# self-balancing-robot.net
KiCad netlist of a schematic drawn in EasyEDA Pro
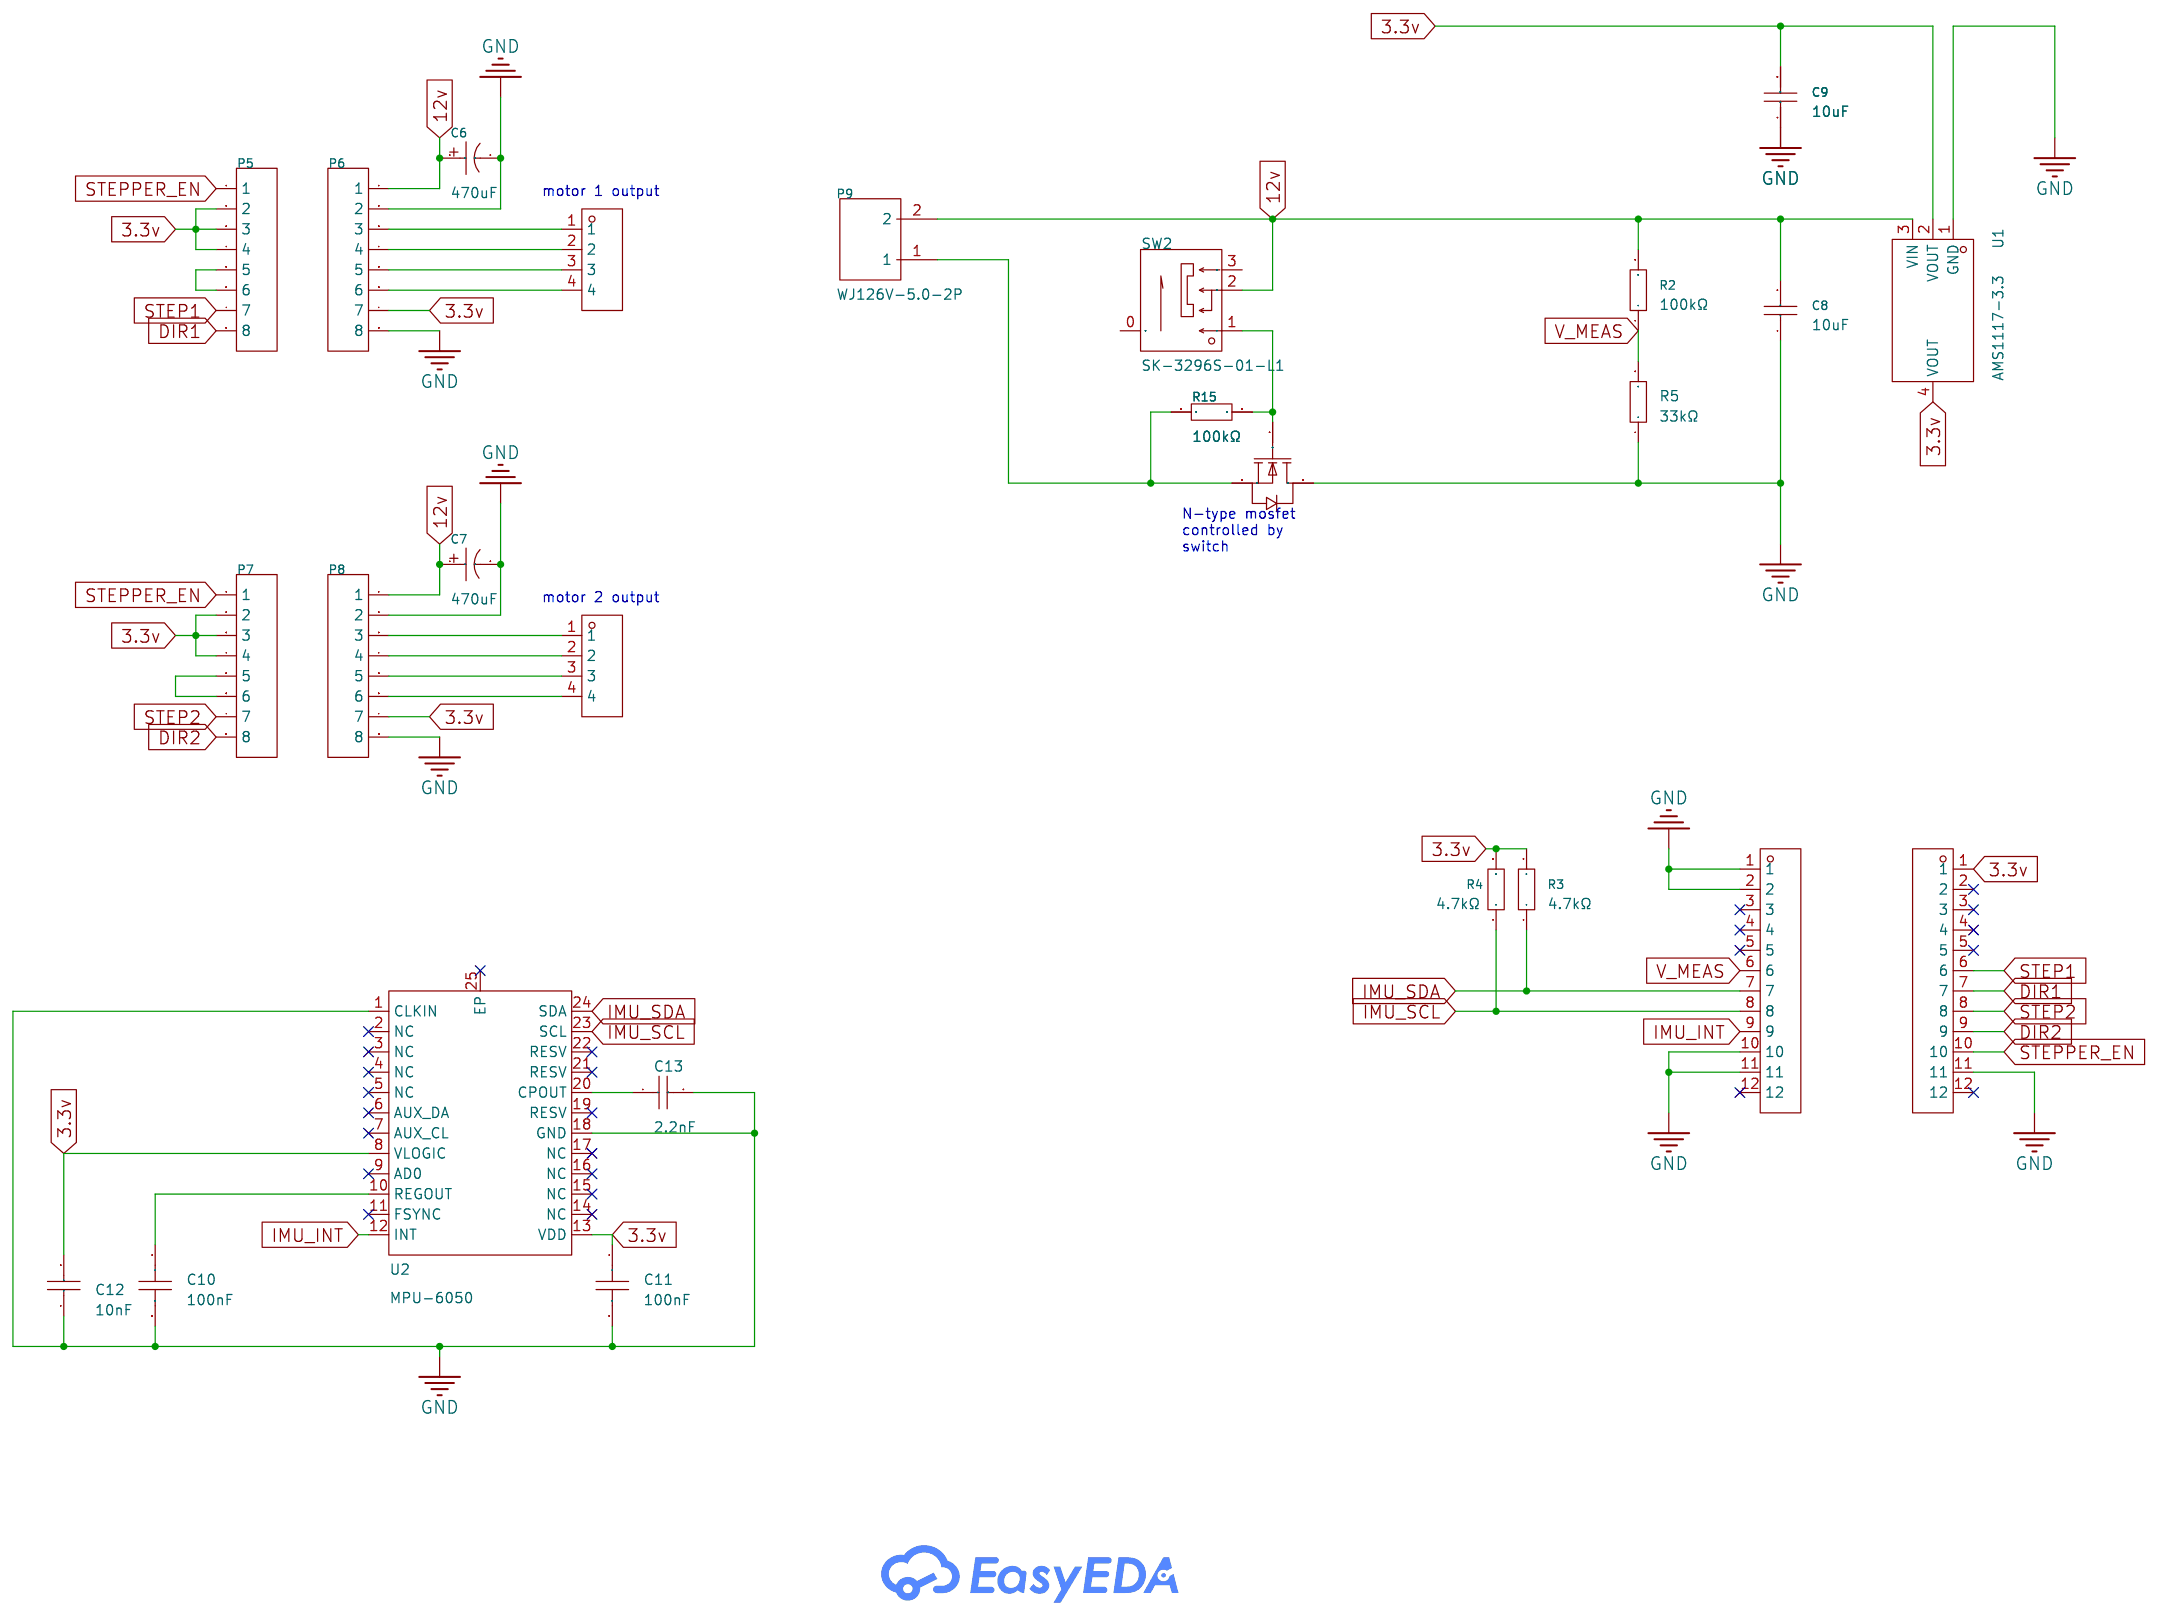
[diagram p0: schematic sheet]

(export (version "E")
  (design (tool "Eeschema 10.0.6"))
  (components
    (comp (ref "C6")
      (value "470uF")
      (footprint "easyedapro:CAP-TH_BD8.0-P3.50-D0.6-FD")
      (fields
        (field (name "Manufacturer Part") "KM477M016F12RR0VH2FP0")
        (field (name "Manufacturer") "CX(承兴)")
      )
      (libsource (lib "easyedapro") (part "470uf16v"))
    )
    (comp (ref "C7")
      (value "470uF")
      (footprint "easyedapro:CAP-TH_BD8.0-P3.50-D0.6-FD")
      (fields
        (field (name "Manufacturer Part") "KM477M016F12RR0VH2FP0")
        (field (name "Manufacturer") "CX(承兴)")
      )
      (libsource (lib "easyedapro") (part "470uf16v"))
    )
    (comp (ref "C8")
      (value "10uF")
      (footprint "easyedapro:C1206")
      (fields
        (field (name "Manufacturer Part") "CL31A106KBHNNNE")
        (field (name "Manufacturer") "SAMSUNG(三星)")
      )
      (libsource (lib "easyedapro") (part "CL31A106KBHNNNE"))
    )
    (comp (ref "C9")
      (value "10uF")
      (footprint "easyedapro:C1206")
      (fields
        (field (name "Manufacturer Part") "CL31A106KBHNNNE")
        (field (name "Manufacturer") "SAMSUNG(三星)")
      )
      (libsource (lib "easyedapro") (part "CL31A106KBHNNNE"))
    )
    (comp (ref "C10")
      (value "100nF")
      (footprint "easyedapro:C0402")
      (description "Capacitance:100nF Tolerance:±10% Tolerance:±10% Voltage Rating:16V Temperature Coefficient:X7R")
      (fields
        (field (name "Manufacturer Part") "CL05B104KO5NNNC")
        (field (name "Manufacturer") "SAMSUNG(三星)")
      )
      (libsource (lib "easyedapro") (part "CL05B104KO5NNNC"))
    )
    (comp (ref "C11")
      (value "100nF")
      (footprint "easyedapro:C0402")
      (description "Capacitance:100nF Tolerance:±10% Tolerance:±10% Voltage Rating:16V Temperature Coefficient:X7R")
      (fields
        (field (name "Manufacturer Part") "CL05B104KO5NNNC")
        (field (name "Manufacturer") "SAMSUNG(三星)")
      )
      (libsource (lib "easyedapro") (part "CL05B104KO5NNNC"))
    )
    (comp (ref "C12")
      (value "10nF")
      (footprint "easyedapro:C0402")
      (description "Capacitance:10nF Tolerance:±10% Tolerance:±10% Voltage Rating:50V Temperature Coefficient:X7R")
      (fields
        (field (name "Manufacturer Part") "CL05B103KB5NNNC")
        (field (name "Manufacturer") "SAMSUNG(三星)")
      )
      (libsource (lib "easyedapro") (part "CL05B103KB5NNNC"))
    )
    (comp (ref "C13")
      (value "2.2nF")
      (footprint "easyedapro:C0402")
      (description "Capacitance:2.2nF Tolerance:±10% Tolerance:±10% Voltage Rating:50V Temperature Coefficient:X7R")
      (fields (field (name "Manufacturer Part") "0402B222K500NT") (field (name "Manufacturer") "FH(风华)"))
      (libsource (lib "easyedapro") (part "0402B222K500NT"))
    )
    (comp (ref "H1")
      (value "PM2.54-1*12")
      (footprint "easyedapro:HDR-TH_12P-P2.54-V-F")
      (fields (field (name "Manufacturer") "ZHOURI(洲日)"))
      (libsource (lib "easyedapro") (part "PM2.54-1*12"))
    )
    (comp (ref "H2")
      (value "PM2.54-1*12")
      (footprint "easyedapro:HDR-TH_12P-P2.54-V-F")
      (fields (field (name "Manufacturer") "ZHOURI(洲日)"))
      (libsource (lib "easyedapro") (part "PM2.54-1*12"))
    )
    (comp (ref "H5")
      (value "2.54-1*4P母")
      (footprint "easyedapro:HDR-TH_4P-P2.54-V-F")
      (fields (field (name "Manufacturer") "BOOMELE(博穆精密)"))
      (libsource (lib "easyedapro") (part "2.54-1*4P母"))
    )
    (comp (ref "H6")
      (value "2.54-1*4P母")
      (footprint "easyedapro:HDR-TH_4P-P2.54-V-F")
      (fields (field (name "Manufacturer") "BOOMELE(博穆精密)"))
      (libsource (lib "easyedapro") (part "2.54-1*4P母"))
    )
    (comp (ref "P5")
      (value "2.54-1*8P母环保")
      (footprint "easyedapro:HDR-TH_8P-P2.54-V-F-1")
      (fields (field (name "Manufacturer") "BOOMELE(博穆精密)"))
      (libsource (lib "easyedapro") (part "Header-Female-2.54_1x8"))
    )
    (comp (ref "P6")
      (value "2.54-1*8P母环保")
      (footprint "easyedapro:HDR-TH_8P-P2.54-V-F-1")
      (fields (field (name "Manufacturer") "BOOMELE(博穆精密)"))
      (libsource (lib "easyedapro") (part "Header-Female-2.54_1x8"))
    )
    (comp (ref "P7")
      (value "2.54-1*8P母环保")
      (footprint "easyedapro:HDR-TH_8P-P2.54-V-F-1")
      (fields (field (name "Manufacturer") "BOOMELE(博穆精密)"))
      (libsource (lib "easyedapro") (part "Header-Female-2.54_1x8"))
    )
    (comp (ref "P8")
      (value "2.54-1*8P母环保")
      (footprint "easyedapro:HDR-TH_8P-P2.54-V-F-1")
      (fields (field (name "Manufacturer") "BOOMELE(博穆精密)"))
      (libsource (lib "easyedapro") (part "Header-Female-2.54_1x8"))
    )
    (comp (ref "P9")
      (value "WJ126V-5.0-2P")
      (footprint "easyedapro:CONN-TH_WJ126V-5.0-2P")
      (fields (field (name "Manufacturer") "KANGNEX(康奈克斯电气)"))
      (libsource (lib "easyedapro") (part "WJ126V-5.0-2P"))
    )
    (comp (ref "Q1")
      (value "AO3400A")
      (footprint "easyedapro:SOT-23-3_L2.9-W1.6-P1.90-LS2.8-BR")
      (fields (field (name "Manufacturer") "AOS"))
      (libsource (lib "easyedapro") (part "AO3400A"))
    )
    (comp (ref "R2")
      (value "100kΩ")
      (footprint "easyedapro:R0402")
      (fields
        (field (name "Manufacturer Part") "0402WGF1003TCE")
        (field (name "Manufacturer") "UNI-ROYAL(厚声)")
      )
      (libsource (lib "easyedapro") (part "0402WGF1003TCE"))
    )
    (comp (ref "R3")
      (value "4.7kΩ")
      (footprint "easyedapro:R0402")
      (fields
        (field (name "Manufacturer Part") "0402WGF4701TCE")
        (field (name "Manufacturer") "UNI-ROYAL(厚声)")
      )
      (libsource (lib "easyedapro") (part "0402WGF4701TCE"))
    )
    (comp (ref "R4")
      (value "4.7kΩ")
      (footprint "easyedapro:R0402")
      (fields
        (field (name "Manufacturer Part") "0402WGF4701TCE")
        (field (name "Manufacturer") "UNI-ROYAL(厚声)")
      )
      (libsource (lib "easyedapro") (part "0402WGF4701TCE"))
    )
    (comp (ref "R5")
      (value "33kΩ")
      (footprint "easyedapro:R0402")
      (fields
        (field (name "Manufacturer Part") "0402WGF3302TCE")
        (field (name "Manufacturer") "UNI-ROYAL(厚声)")
      )
      (libsource (lib "easyedapro") (part "0402WGF3302TCE"))
    )
    (comp (ref "R15")
      (value "100kΩ")
      (footprint "easyedapro:R0402")
      (fields
        (field (name "Manufacturer Part") "0402WGF1003TCE")
        (field (name "Manufacturer") "UNI-ROYAL(厚声)")
      )
      (libsource (lib "easyedapro") (part "0402WGF1003TCE"))
    )
    (comp (ref "SW2")
      (value "SK-3296S-01-L1")
      (footprint "easyedapro:SW-SMD_3P-P1.50_L2.7-W6.6")
      (fields (field (name "Manufacturer") "XKB Connectivity(中国星坤)"))
      (libsource (lib "easyedapro") (part "SK-3296S-01-L1"))
    )
    (comp (ref "U1")
      (value "AMS1117-3.3")
      (footprint "easyedapro:SOT-223-3_L6.5-W3.4-P2.30-LS7.0-BR")
      (fields (field (name "Manufacturer") "AMS"))
      (libsource (lib "easyedapro") (part "AMS1117-3.3"))
    )
    (comp (ref "U2")
      (value "MPU-6050")
      (footprint "easyedapro:QFN-24_L4.0-W4.0-P0.50-BL-EP2.7")
      (fields (field (name "Manufacturer") "TDK InvenSense(应美盛)"))
      (libsource (lib "easyedapro") (part "MPU-6050_C24112"))
    )
  )
  (nets
    (net (code "1") (name "3.3v") (class "Default")
      (node (ref "C11") (pin "1") (pinfunction "1_1") (pintype "unspecified"))
      (node (ref "C12") (pin "2") (pinfunction "2_2") (pintype "input"))
      (node (ref "C9") (pin "2") (pinfunction "2_2") (pintype "input"))
      (node (ref "H2") (pin "1") (pinfunction "1_1") (pintype "unspecified"))
      (node (ref "P5") (pin "2") (pinfunction "2_2") (pintype "input"))
      (node (ref "P5") (pin "3") (pinfunction "3_3") (pintype "input"))
      (node (ref "P5") (pin "4") (pinfunction "4_4") (pintype "input"))
      (node (ref "P6") (pin "7") (pinfunction "7_7") (pintype "input"))
      (node (ref "P7") (pin "2") (pinfunction "2_2") (pintype "input"))
      (node (ref "P7") (pin "3") (pinfunction "3_3") (pintype "input"))
      (node (ref "P7") (pin "4") (pinfunction "4_4") (pintype "input"))
      (node (ref "P8") (pin "7") (pinfunction "7_7") (pintype "input"))
      (node (ref "R3") (pin "2") (pinfunction "2_2") (pintype "input"))
      (node (ref "R4") (pin "2") (pinfunction "2_2") (pintype "input"))
      (node (ref "U1") (pin "2") (pinfunction "VOUT_2") (pintype "unspecified"))
      (node (ref "U1") (pin "4") (pinfunction "VOUT_4") (pintype "unspecified"))
      (node (ref "U2") (pin "13") (pinfunction "VDD_13") (pintype "unspecified"))
      (node (ref "U2") (pin "8") (pinfunction "VLOGIC_8") (pintype "unspecified"))
    )
    (net (code "2") (name "12v") (class "Default")
      (node (ref "C6") (pin "1") (pinfunction "1_1") (pintype "input"))
      (node (ref "C7") (pin "1") (pinfunction "1_1") (pintype "input"))
      (node (ref "C8") (pin "2") (pinfunction "2_2") (pintype "input"))
      (node (ref "P6") (pin "1") (pinfunction "1_1") (pintype "input"))
      (node (ref "P8") (pin "1") (pinfunction "1_1") (pintype "input"))
      (node (ref "P9") (pin "2") (pinfunction "2_2") (pintype "input"))
      (node (ref "R2") (pin "2") (pinfunction "2_2") (pintype "input"))
      (node (ref "SW2") (pin "2") (pinfunction "2_2") (pintype "unspecified"))
      (node (ref "U1") (pin "3") (pinfunction "VIN_3") (pintype "unspecified"))
    )
    (net (code "3") (name "DIR1") (class "Default")
      (node (ref "H2") (pin "7") (pinfunction "7_7") (pintype "unspecified"))
      (node (ref "P5") (pin "8") (pinfunction "8_8") (pintype "input"))
    )
    (net (code "4") (name "DIR2") (class "Default")
      (node (ref "H2") (pin "9") (pinfunction "9_9") (pintype "unspecified"))
      (node (ref "P7") (pin "8") (pinfunction "8_8") (pintype "input"))
    )
    (net (code "5") (name "GND") (class "Default")
      (node (ref "C10") (pin "2") (pinfunction "2_2") (pintype "unspecified"))
      (node (ref "C11") (pin "2") (pinfunction "2_2") (pintype "unspecified"))
      (node (ref "C12") (pin "1") (pinfunction "1_1") (pintype "input"))
      (node (ref "C13") (pin "2") (pinfunction "2_2") (pintype "input"))
      (node (ref "C6") (pin "2") (pinfunction "2_2") (pintype "input"))
      (node (ref "C7") (pin "2") (pinfunction "2_2") (pintype "input"))
      (node (ref "C8") (pin "1") (pinfunction "1_1") (pintype "input"))
      (node (ref "C9") (pin "1") (pinfunction "1_1") (pintype "input"))
      (node (ref "H1") (pin "1") (pinfunction "1_1") (pintype "unspecified"))
      (node (ref "H1") (pin "10") (pinfunction "10_10") (pintype "unspecified"))
      (node (ref "H1") (pin "11") (pinfunction "11_11") (pintype "unspecified"))
      (node (ref "H1") (pin "2") (pinfunction "2_2") (pintype "unspecified"))
      (node (ref "H2") (pin "11") (pinfunction "11_11") (pintype "unspecified"))
      (node (ref "P6") (pin "2") (pinfunction "2_2") (pintype "input"))
      (node (ref "P6") (pin "8") (pinfunction "8_8") (pintype "input"))
      (node (ref "P8") (pin "2") (pinfunction "2_2") (pintype "input"))
      (node (ref "P8") (pin "8") (pinfunction "8_8") (pintype "input"))
      (node (ref "Q1") (pin "3") (pinfunction "D_3") (pintype "unspecified"))
      (node (ref "R5") (pin "1") (pinfunction "1_1") (pintype "input"))
      (node (ref "U1") (pin "1") (pinfunction "GND_1") (pintype "unspecified"))
      (node (ref "U2") (pin "1") (pinfunction "CLKIN_1") (pintype "unspecified"))
      (node (ref "U2") (pin "18") (pinfunction "GND_18") (pintype "unspecified"))
    )
    (net (code "6") (name "IMU_INT") (class "Default")
      (node (ref "H1") (pin "9") (pinfunction "9_9") (pintype "unspecified"))
      (node (ref "U2") (pin "12") (pinfunction "INT_12") (pintype "unspecified"))
    )
    (net (code "7") (name "IMU_SCL") (class "Default")
      (node (ref "H1") (pin "8") (pinfunction "8_8") (pintype "unspecified"))
      (node (ref "R4") (pin "1") (pinfunction "1_1") (pintype "input"))
      (node (ref "U2") (pin "23") (pinfunction "SCL_23") (pintype "unspecified"))
    )
    (net (code "8") (name "IMU_SDA") (class "Default")
      (node (ref "H1") (pin "7") (pinfunction "7_7") (pintype "unspecified"))
      (node (ref "R3") (pin "1") (pinfunction "1_1") (pintype "input"))
      (node (ref "U2") (pin "24") (pinfunction "SDA_24") (pintype "unspecified"))
    )
    (net (code "9") (name "Net-(H5-Pad1)") (class "Default")
      (node (ref "H5") (pin "1") (pinfunction "1_1") (pintype "input"))
      (node (ref "P6") (pin "3") (pinfunction "3_3") (pintype "input"))
    )
    (net (code "10") (name "Net-(H5-Pad2)") (class "Default")
      (node (ref "H5") (pin "2") (pinfunction "2_2") (pintype "input"))
      (node (ref "P6") (pin "4") (pinfunction "4_4") (pintype "input"))
    )
    (net (code "11") (name "Net-(H5-Pad3)") (class "Default")
      (node (ref "H5") (pin "3") (pinfunction "3_3") (pintype "input"))
      (node (ref "P6") (pin "5") (pinfunction "5_5") (pintype "input"))
    )
    (net (code "12") (name "Net-(H5-Pad4)") (class "Default")
      (node (ref "H5") (pin "4") (pinfunction "4_4") (pintype "input"))
      (node (ref "P6") (pin "6") (pinfunction "6_6") (pintype "input"))
    )
    (net (code "13") (name "Net-(H6-Pad1)") (class "Default")
      (node (ref "H6") (pin "1") (pinfunction "1_1") (pintype "input"))
      (node (ref "P8") (pin "3") (pinfunction "3_3") (pintype "input"))
    )
    (net (code "14") (name "Net-(H6-Pad2)") (class "Default")
      (node (ref "H6") (pin "2") (pinfunction "2_2") (pintype "input"))
      (node (ref "P8") (pin "4") (pinfunction "4_4") (pintype "input"))
    )
    (net (code "15") (name "Net-(H6-Pad3)") (class "Default")
      (node (ref "H6") (pin "3") (pinfunction "3_3") (pintype "input"))
      (node (ref "P8") (pin "5") (pinfunction "5_5") (pintype "input"))
    )
    (net (code "16") (name "Net-(H6-Pad4)") (class "Default")
      (node (ref "H6") (pin "4") (pinfunction "4_4") (pintype "input"))
      (node (ref "P8") (pin "6") (pinfunction "6_6") (pintype "input"))
    )
    (net (code "17") (name "Net-(P5-Pad5)") (class "Default")
      (node (ref "P5") (pin "5") (pinfunction "5_5") (pintype "input"))
      (node (ref "P5") (pin "6") (pinfunction "6_6") (pintype "input"))
    )
    (net (code "18") (name "Net-(P7-Pad5)") (class "Default")
      (node (ref "P7") (pin "5") (pinfunction "5_5") (pintype "input"))
      (node (ref "P7") (pin "6") (pinfunction "6_6") (pintype "input"))
    )
    (net (code "19") (name "Net-(Q1-G)") (class "Default")
      (node (ref "Q1") (pin "1") (pinfunction "G_1") (pintype "unspecified"))
      (node (ref "R15") (pin "1") (pinfunction "1_1") (pintype "input"))
      (node (ref "SW2") (pin "1") (pinfunction "1_1") (pintype "unspecified"))
    )
    (net (code "20") (name "Net-(Q1-S)") (class "Default")
      (node (ref "P9") (pin "1") (pinfunction "1_1") (pintype "input"))
      (node (ref "Q1") (pin "2") (pinfunction "S_2") (pintype "unspecified"))
      (node (ref "R15") (pin "2") (pinfunction "2_2") (pintype "input"))
    )
    (net (code "21") (name "Net-(U2-CPOUT)") (class "Default")
      (node (ref "C13") (pin "1") (pinfunction "1_1") (pintype "input"))
      (node (ref "U2") (pin "20") (pinfunction "CPOUT_20") (pintype "unspecified"))
    )
    (net (code "22") (name "Net-(U2-REGOUT)") (class "Default")
      (node (ref "C10") (pin "1") (pinfunction "1_1") (pintype "unspecified"))
      (node (ref "U2") (pin "10") (pinfunction "REGOUT_10") (pintype "unspecified"))
    )
    (net (code "23") (name "STEP1") (class "Default")
      (node (ref "H2") (pin "6") (pinfunction "6_6") (pintype "unspecified"))
      (node (ref "P5") (pin "7") (pinfunction "7_7") (pintype "input"))
    )
    (net (code "24") (name "STEP2") (class "Default")
      (node (ref "H2") (pin "8") (pinfunction "8_8") (pintype "unspecified"))
      (node (ref "P7") (pin "7") (pinfunction "7_7") (pintype "input"))
    )
    (net (code "25") (name "STEPPER_EN") (class "Default")
      (node (ref "H2") (pin "10") (pinfunction "10_10") (pintype "unspecified"))
      (node (ref "P5") (pin "1") (pinfunction "1_1") (pintype "input"))
      (node (ref "P7") (pin "1") (pinfunction "1_1") (pintype "input"))
    )
    (net (code "26") (name "V_MEAS") (class "Default")
      (node (ref "H1") (pin "6") (pinfunction "6_6") (pintype "unspecified"))
      (node (ref "R2") (pin "1") (pinfunction "1_1") (pintype "input"))
      (node (ref "R5") (pin "2") (pinfunction "2_2") (pintype "input"))
    )
    (net (code "27") (name "unconnected-(H1-Pad3)") (class "Default")
      (node (ref "H1") (pin "3") (pinfunction "3_3") (pintype "unspecified+no_connect"))
    )
    (net (code "28") (name "unconnected-(H1-Pad4)") (class "Default")
      (node (ref "H1") (pin "4") (pinfunction "4_4") (pintype "unspecified+no_connect"))
    )
    (net (code "29") (name "unconnected-(H1-Pad5)") (class "Default")
      (node (ref "H1") (pin "5") (pinfunction "5_5") (pintype "unspecified+no_connect"))
    )
    (net (code "30") (name "unconnected-(H1-Pad12)") (class "Default")
      (node (ref "H1") (pin "12") (pinfunction "12_12") (pintype "unspecified+no_connect"))
    )
    (net (code "31") (name "unconnected-(H2-Pad2)") (class "Default")
      (node (ref "H2") (pin "2") (pinfunction "2_2") (pintype "unspecified+no_connect"))
    )
    (net (code "32") (name "unconnected-(H2-Pad3)") (class "Default")
      (node (ref "H2") (pin "3") (pinfunction "3_3") (pintype "unspecified+no_connect"))
    )
    (net (code "33") (name "unconnected-(H2-Pad4)") (class "Default")
      (node (ref "H2") (pin "4") (pinfunction "4_4") (pintype "unspecified+no_connect"))
    )
    (net (code "34") (name "unconnected-(H2-Pad5)") (class "Default")
      (node (ref "H2") (pin "5") (pinfunction "5_5") (pintype "unspecified+no_connect"))
    )
    (net (code "35") (name "unconnected-(H2-Pad12)") (class "Default")
      (node (ref "H2") (pin "12") (pinfunction "12_12") (pintype "unspecified+no_connect"))
    )
    (net (code "36") (name "unconnected-(SW2-Pad0)") (class "Default")
      (node (ref "SW2") (pin "0") (pinfunction "0_0") (pintype "unspecified"))
    )
    (net (code "37") (name "unconnected-(SW2-Pad3)") (class "Default")
      (node (ref "SW2") (pin "3") (pinfunction "3_3") (pintype "unspecified"))
    )
    (net (code "38") (name "unconnected-(U2-AD0-Pad9)") (class "Default")
      (node (ref "U2") (pin "9") (pinfunction "AD0_9") (pintype "unspecified+no_connect"))
    )
    (net (code "39") (name "unconnected-(U2-AUX_CL-Pad7)") (class "Default")
      (node (ref "U2") (pin "7") (pinfunction "AUX_CL_7") (pintype "unspecified+no_connect"))
    )
    (net (code "40") (name "unconnected-(U2-AUX_DA-Pad6)") (class "Default")
      (node (ref "U2") (pin "6") (pinfunction "AUX_DA_6") (pintype "unspecified+no_connect"))
    )
    (net (code "41") (name "unconnected-(U2-EP-Pad25)") (class "Default")
      (node (ref "U2") (pin "25") (pinfunction "EP_25") (pintype "unspecified+no_connect"))
    )
    (net (code "42") (name "unconnected-(U2-FSYNC-Pad11)") (class "Default")
      (node (ref "U2") (pin "11") (pinfunction "FSYNC_11") (pintype "unspecified+no_connect"))
    )
    (net (code "43") (name "unconnected-(U2-NC-Pad2)") (class "Default")
      (node (ref "U2") (pin "2") (pinfunction "NC_2") (pintype "unspecified+no_connect"))
    )
    (net (code "44") (name "unconnected-(U2-NC-Pad3)") (class "Default")
      (node (ref "U2") (pin "3") (pinfunction "NC_3") (pintype "unspecified+no_connect"))
    )
    (net (code "45") (name "unconnected-(U2-NC-Pad4)") (class "Default")
      (node (ref "U2") (pin "4") (pinfunction "NC_4") (pintype "unspecified+no_connect"))
    )
    (net (code "46") (name "unconnected-(U2-NC-Pad5)") (class "Default")
      (node (ref "U2") (pin "5") (pinfunction "NC_5") (pintype "unspecified+no_connect"))
    )
    (net (code "47") (name "unconnected-(U2-NC-Pad14)") (class "Default")
      (node (ref "U2") (pin "14") (pinfunction "NC_14") (pintype "unspecified+no_connect"))
    )
    (net (code "48") (name "unconnected-(U2-NC-Pad15)") (class "Default")
      (node (ref "U2") (pin "15") (pinfunction "NC_15") (pintype "unspecified+no_connect"))
    )
    (net (code "49") (name "unconnected-(U2-NC-Pad16)") (class "Default")
      (node (ref "U2") (pin "16") (pinfunction "NC_16") (pintype "unspecified+no_connect"))
    )
    (net (code "50") (name "unconnected-(U2-NC-Pad17)") (class "Default")
      (node (ref "U2") (pin "17") (pinfunction "NC_17") (pintype "unspecified+no_connect"))
    )
    (net (code "51") (name "unconnected-(U2-RESV-Pad19)") (class "Default")
      (node (ref "U2") (pin "19") (pinfunction "RESV_19") (pintype "unspecified+no_connect"))
    )
    (net (code "52") (name "unconnected-(U2-RESV-Pad21)") (class "Default")
      (node (ref "U2") (pin "21") (pinfunction "RESV_21") (pintype "unspecified+no_connect"))
    )
    (net (code "53") (name "unconnected-(U2-RESV-Pad22)") (class "Default")
      (node (ref "U2") (pin "22") (pinfunction "RESV_22") (pintype "unspecified+no_connect"))
    )
  )
)
